# GSR.net
KiCad netlist of a schematic drawn in Altium Designer
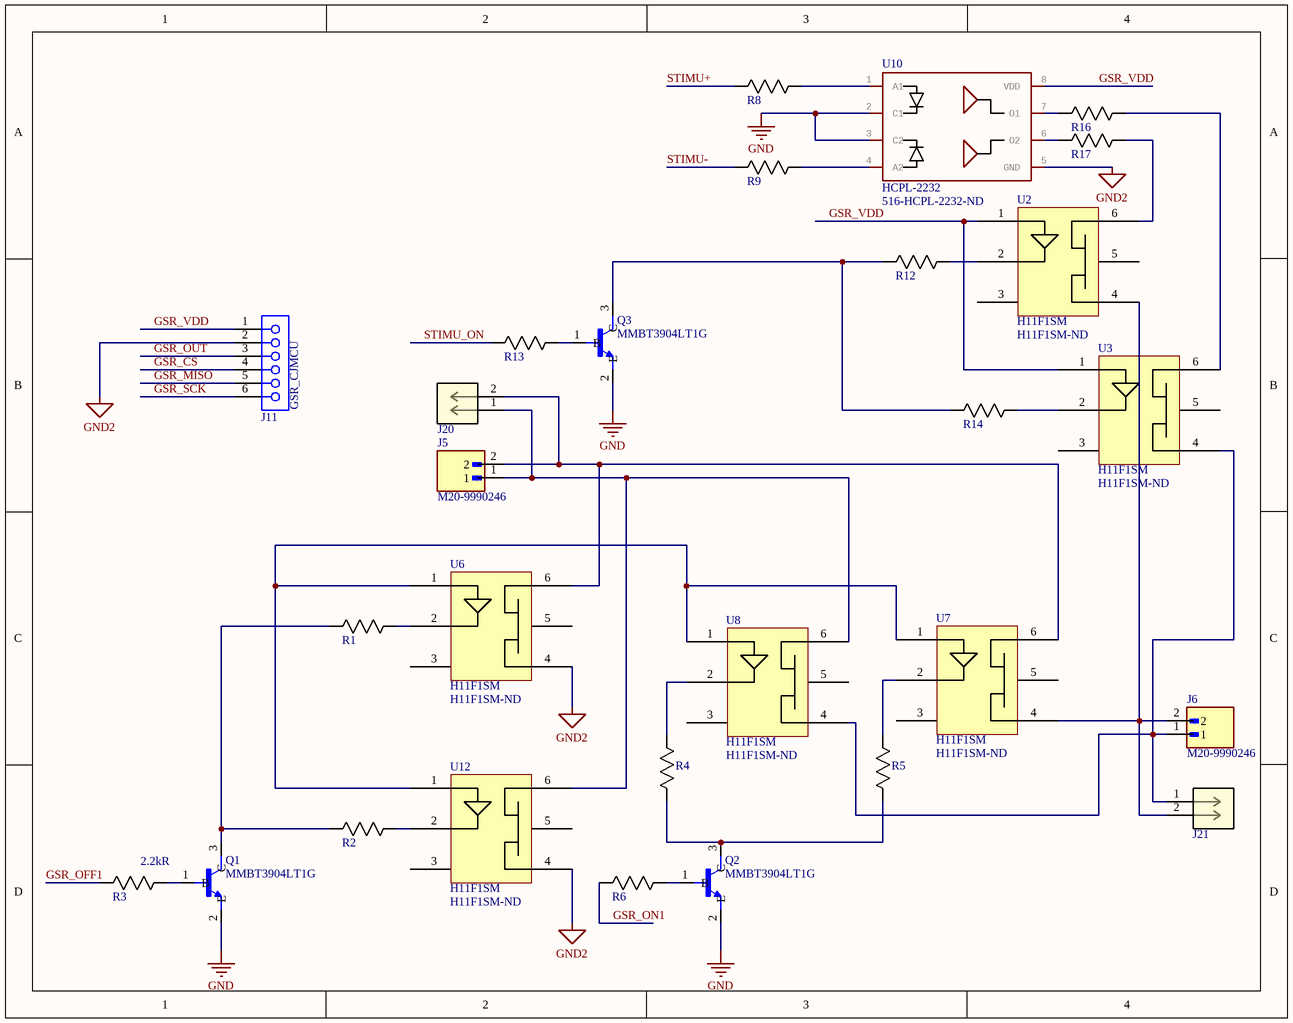
[diagram p0: GSR.SchDoc]

(export (version "E")
  (design (tool "Eeschema 10.0.6"))
  (components
    (comp (ref "J5")
      (value "M20-9990246")
      (footprint "HARWIN_M20-9990246")
      (description "2.54mm (0.1) Pitch SIL Vertical Throughboard Pin Header, 6.1mm mating pin height, tin, 2 contacts")
      (fields (field (name "MF") "Harwin"))
      (libsource (lib "koncept") (part "M20-9990246"))
    )
    (comp (ref "J6")
      (value "M20-9990246")
      (footprint "HARWIN_M20-9990246")
      (description "2.54mm (0.1) Pitch SIL Vertical Throughboard Pin Header, 6.1mm mating pin height, tin, 2 contacts")
      (fields (field (name "MF") "Harwin"))
      (libsource (lib "") (part "M20-9990246_1"))
    )
    (comp (ref "J11")
      (value "61300611821")
      (footprint "HEADER_SOCKET_6")
      (description "WR-PHD Socket Header, THT, Vertical, pitch 2.54mm, 1 Row, 6P")
      (fields (field (name "MANUFACTURER") "Wurth Elektronik"))
      (libsource (lib "Connectors") (part "HEADER_SOCKET_6"))
    )
    (comp (ref "J20")
      (value "B2P-VH")
      (footprint "CONN_B2P-VH_JST")
      (description "VH Non-RoHS Compliant 2003 Vertical Connector Header -25C~85C 10A 250V 0.303 7.70mm")
      (fields (field (name "MANUFACTURER") "JST"))
      (libsource (lib "") (part "B2P-VH_1"))
    )
    (comp (ref "J21")
      (value "B2P-VH")
      (footprint "CONN_B2P-VH_JST")
      (description "VH Non-RoHS Compliant 2003 Vertical Connector Header -25C~85C 10A 250V 0.303 7.70mm")
      (fields (field (name "MANUFACTURER") "JST"))
      (libsource (lib "Connectors") (part "B2P-VH"))
    )
    (comp (ref "Q1")
      (value "MMBT3904LT1G")
      (footprint "SOT95P240X111-3N")
      (fields (field (name "MF") "ON Semiconductor"))
      (libsource (lib "Passive") (part "MMBT3904LT1G"))
    )
    (comp (ref "Q2")
      (value "MMBT3904LT1G")
      (footprint "SOT95P240X111-3N")
      (fields (field (name "MF") "ON Semiconductor"))
      (libsource (lib "Passive") (part "MMBT3904LT1G"))
    )
    (comp (ref "Q3")
      (value "MMBT3904LT1G")
      (footprint "SOT95P240X111-3N")
      (fields (field (name "MF") "ON Semiconductor"))
      (libsource (lib "Passive") (part "MMBT3904LT1G"))
    )
    (comp (ref "R1")
      (value "RMCF1206FT220R")
      (footprint "STA_RMCF1206_STP-L")
      (description "No Description Available")
      (fields (field (name "COPYRIGHT") "Copyright (C) 2025 Ultra Librarian. All rights reserved."))
      (libsource (lib "Passive") (part "RMCF1206FT220R"))
    )
    (comp (ref "R2")
      (value "RMCF1206FT220R")
      (footprint "STA_RMCF1206_STP-L")
      (description "No Description Available")
      (fields (field (name "COPYRIGHT") "Copyright (C) 2025 Ultra Librarian. All rights reserved."))
      (libsource (lib "Passive") (part "RMCF1206FT220R"))
    )
    (comp (ref "R3")
      (value "CRGCQ1206F2K2")
      (footprint "STA_RMCF1206_STP-L")
      (description "SMD Chip Resistor, 2.2 kOhm, ± 1%, 250 mW, 1206 [3216 Metric], Thick Film, General Purpose")
      (fields (field (name "MANUFACTURER") "TE Connectivity") (field (name "RESISTANCE") "2.2kR"))
      (libsource (lib "Passive") (part "R1206F2K2"))
    )
    (comp (ref "R4")
      (value "RMCF1206FT220R")
      (footprint "STA_RMCF1206_STP-L")
      (description "No Description Available")
      (fields (field (name "COPYRIGHT") "Copyright (C) 2025 Ultra Librarian. All rights reserved."))
      (libsource (lib "Passive") (part "RMCF1206FT220R"))
    )
    (comp (ref "R5")
      (value "RMCF1206FT220R")
      (footprint "STA_RMCF1206_STP-L")
      (description "No Description Available")
      (fields (field (name "COPYRIGHT") "Copyright (C) 2025 Ultra Librarian. All rights reserved."))
      (libsource (lib "Passive") (part "RMCF1206FT220R"))
    )
    (comp (ref "R6")
      (value "CRGCQ1206F2K2")
      (footprint "STA_RMCF1206_STP-L")
      (description "SMD Chip Resistor, 2.2 kOhm, ± 1%, 250 mW, 1206 [3216 Metric], Thick Film, General Purpose")
      (fields (field (name "MANUFACTURER") "TE Connectivity"))
      (libsource (lib "Passive") (part "R1206F2K2"))
    )
    (comp (ref "R8")
      (value "RMCF1206FT220R")
      (footprint "STA_RMCF1206_STP-L")
      (description "No Description Available")
      (fields (field (name "COPYRIGHT") "Copyright (C) 2025 Ultra Librarian. All rights reserved."))
      (libsource (lib "Passive") (part "RMCF1206FT220R"))
    )
    (comp (ref "R9")
      (value "RMCF1206FT220R")
      (footprint "STA_RMCF1206_STP-L")
      (description "No Description Available")
      (fields (field (name "COPYRIGHT") "Copyright (C) 2025 Ultra Librarian. All rights reserved."))
      (libsource (lib "Passive") (part "RMCF1206FT220R"))
    )
    (comp (ref "R12")
      (value "RMCF1206FT220R")
      (footprint "STA_RMCF1206_STP-L")
      (description "No Description Available")
      (fields (field (name "COPYRIGHT") "Copyright (C) 2025 Ultra Librarian. All rights reserved."))
      (libsource (lib "Passive") (part "RMCF1206FT220R"))
    )
    (comp (ref "R13")
      (value "CRGCQ1206F2K2")
      (footprint "STA_RMCF1206_STP-L")
      (description "SMD Chip Resistor, 2.2 kOhm, ± 1%, 250 mW, 1206 [3216 Metric], Thick Film, General Purpose")
      (fields (field (name "MANUFACTURER") "TE Connectivity"))
      (libsource (lib "Passive") (part "R1206F2K2"))
    )
    (comp (ref "R14")
      (value "RMCF1206FT220R")
      (footprint "STA_RMCF1206_STP-L")
      (description "No Description Available")
      (fields (field (name "COPYRIGHT") "Copyright (C) 2025 Ultra Librarian. All rights reserved."))
      (libsource (lib "Passive") (part "RMCF1206FT220R"))
    )
    (comp (ref "R16")
      (value "CRGCQ1206F2K2")
      (footprint "STA_RMCF1206_STP-L")
      (description "SMD Chip Resistor, 2.2 kOhm, ± 1%, 250 mW, 1206 [3216 Metric], Thick Film, General Purpose")
      (fields (field (name "MANUFACTURER") "TE Connectivity"))
      (libsource (lib "Passive") (part "R1206F2K2"))
    )
    (comp (ref "R17")
      (value "CRGCQ1206F2K2")
      (footprint "STA_RMCF1206_STP-L")
      (description "SMD Chip Resistor, 2.2 kOhm, ± 1%, 250 mW, 1206 [3216 Metric], Thick Film, General Purpose")
      (fields (field (name "MANUFACTURER") "TE Connectivity"))
      (libsource (lib "Passive") (part "R1206F2K2"))
    )
    (comp (ref "U2")
      (value "H11F1SM")
      (footprint "OPTOCOUPLER_H11F3SR2M")
      (description "Optocoupler DC-IN 1-CH Transistor DC-OUT 6-Pin PDIP SMD White Bulk")
      (fields (field (name "MANUFACTURER") "onsemi") (field (name "SUPPLIER PART NUMBER 1") "H11F1SM-ND"))
      (libsource (lib "koncept") (part "H11F1SM"))
    )
    (comp (ref "U3")
      (value "H11F1SM")
      (footprint "OPTOCOUPLER_H11F3SR2M")
      (description "Optocoupler DC-IN 1-CH Transistor DC-OUT 6-Pin PDIP SMD White Bulk")
      (fields (field (name "MANUFACTURER") "onsemi") (field (name "SUPPLIER PART NUMBER 1") "H11F1SM-ND"))
      (libsource (lib "koncept") (part "H11F1SM"))
    )
    (comp (ref "U6")
      (value "H11F1SM")
      (footprint "OPTOCOUPLER_H11F3SR2M")
      (description "Optocoupler DC-IN 1-CH Transistor DC-OUT 6-Pin PDIP SMD White Bulk")
      (fields (field (name "MANUFACTURER") "onsemi") (field (name "SUPPLIER PART NUMBER 1") "H11F1SM-ND"))
      (libsource (lib "koncept") (part "H11F1SM"))
    )
    (comp (ref "U7")
      (value "H11F1SM")
      (footprint "OPTOCOUPLER_H11F3SR2M")
      (description "Optocoupler DC-IN 1-CH Transistor DC-OUT 6-Pin PDIP SMD White Bulk")
      (fields (field (name "MANUFACTURER") "onsemi") (field (name "SUPPLIER PART NUMBER 1") "H11F1SM-ND"))
      (libsource (lib "koncept") (part "H11F1SM"))
    )
    (comp (ref "U8")
      (value "H11F1SM")
      (footprint "OPTOCOUPLER_H11F3SR2M")
      (description "Optocoupler DC-IN 1-CH Transistor DC-OUT 6-Pin PDIP SMD White Bulk")
      (fields (field (name "MANUFACTURER") "onsemi") (field (name "SUPPLIER PART NUMBER 1") "H11F1SM-ND"))
      (libsource (lib "koncept") (part "H11F1SM"))
    )
    (comp (ref "U10")
      (value "HCPL-2232")
      (footprint "DIL08")
      (description "Optocoupler Logic Output Totem-Pole DC Input 2 Channel 8-Pin Plastic Dip Tube")
      (fields
        (field (name "MANUFACTURER") "Broadcom Avago")
        (field (name "SUPPLIER PART NUMBER 1") "516-HCPL-2232-ND")
      )
      (libsource (lib "koncept") (part "HCPL-2232"))
    )
    (comp (ref "U12")
      (value "H11F1SM")
      (footprint "OPTOCOUPLER_H11F3SR2M")
      (description "Optocoupler DC-IN 1-CH Transistor DC-OUT 6-Pin PDIP SMD White Bulk")
      (fields (field (name "MANUFACTURER") "onsemi") (field (name "SUPPLIER PART NUMBER 1") "H11F1SM-ND"))
      (libsource (lib "koncept") (part "H11F1SM"))
    )
  )
  (nets
    (net (code "1") (name "/GSR_CS") (class "Default")
      (node (ref "J11") (pin "4") (pinfunction "4_4") (pintype "passive"))
    )
    (net (code "2") (name "/GSR_MISO") (class "Default")
      (node (ref "J11") (pin "5") (pinfunction "5_5") (pintype "passive"))
    )
    (net (code "3") (name "/GSR_OFF1") (class "Default")
      (node (ref "R3") (pin "1") (pinfunction "1_1") (pintype "passive"))
    )
    (net (code "4") (name "/GSR_ON1") (class "Default")
      (node (ref "R6") (pin "1") (pinfunction "1_1") (pintype "passive"))
    )
    (net (code "5") (name "/GSR_OUT") (class "Default")
      (node (ref "J11") (pin "3") (pinfunction "3_3") (pintype "passive"))
    )
    (net (code "6") (name "/GSR_SCK") (class "Default")
      (node (ref "J11") (pin "6") (pinfunction "6_6") (pintype "passive"))
    )
    (net (code "7") (name "/GSR_VDD") (class "Default")
      (node (ref "J11") (pin "1") (pinfunction "1_1") (pintype "passive"))
      (node (ref "U10") (pin "8") (pinfunction "VDD_8") (pintype "power_in"))
      (node (ref "U2") (pin "1") (pinfunction "1_1") (pintype "passive"))
      (node (ref "U3") (pin "1") (pinfunction "1_1") (pintype "passive"))
    )
    (net (code "8") (name "/STIMU+") (class "Default")
      (node (ref "R8") (pin "1") (pinfunction "1_1") (pintype "passive"))
    )
    (net (code "9") (name "/STIMU-") (class "Default")
      (node (ref "R9") (pin "1") (pinfunction "1_1") (pintype "passive"))
    )
    (net (code "10") (name "/STIMU_ON") (class "Default")
      (node (ref "R13") (pin "1") (pinfunction "1_1") (pintype "passive"))
    )
    (net (code "11") (name "GND") (class "Default")
      (node (ref "Q1") (pin "2") (pinfunction "E_2") (pintype "passive"))
      (node (ref "Q2") (pin "2") (pinfunction "E_2") (pintype "passive"))
      (node (ref "Q3") (pin "2") (pinfunction "E_2") (pintype "passive"))
      (node (ref "U10") (pin "2") (pinfunction "C1_2") (pintype "power_in"))
      (node (ref "U10") (pin "3") (pinfunction "C2_3") (pintype "power_in"))
    )
    (net (code "12") (name "GND2") (class "Default")
      (node (ref "J11") (pin "2") (pinfunction "2_2") (pintype "passive"))
      (node (ref "U10") (pin "5") (pinfunction "GND_5") (pintype "power_in"))
      (node (ref "U12") (pin "4") (pinfunction "4_4") (pintype "passive"))
      (node (ref "U6") (pin "4") (pinfunction "4_4") (pintype "passive"))
    )
    (net (code "13") (name "Net-(J20-Pad1)") (class "Default")
      (node (ref "J20") (pin "1") (pinfunction "1_1") (pintype "passive"))
      (node (ref "J5") (pin "1") (pinfunction "1_1") (pintype "passive"))
      (node (ref "U12") (pin "6") (pinfunction "6_6") (pintype "passive"))
      (node (ref "U8") (pin "6") (pinfunction "6_6") (pintype "passive"))
    )
    (net (code "14") (name "Net-(J20-Pad2)") (class "Default")
      (node (ref "J20") (pin "2") (pinfunction "2_2") (pintype "passive"))
      (node (ref "J5") (pin "2") (pinfunction "2_2") (pintype "passive"))
      (node (ref "U6") (pin "6") (pinfunction "6_6") (pintype "passive"))
      (node (ref "U7") (pin "6") (pinfunction "6_6") (pintype "passive"))
    )
    (net (code "15") (name "Net-(J21-Pad1)") (class "Default")
      (node (ref "J21") (pin "1") (pinfunction "1_1") (pintype "passive"))
      (node (ref "J6") (pin "1") (pinfunction "1_1") (pintype "passive"))
      (node (ref "U3") (pin "4") (pinfunction "4_4") (pintype "passive"))
      (node (ref "U8") (pin "4") (pinfunction "4_4") (pintype "passive"))
    )
    (net (code "16") (name "Net-(J21-Pad2)") (class "Default")
      (node (ref "J21") (pin "2") (pinfunction "2_2") (pintype "passive"))
      (node (ref "J6") (pin "2") (pinfunction "2_2") (pintype "passive"))
      (node (ref "U2") (pin "4") (pinfunction "4_4") (pintype "passive"))
      (node (ref "U7") (pin "4") (pinfunction "4_4") (pintype "passive"))
    )
    (net (code "17") (name "Net-(Q1-B)") (class "Default")
      (node (ref "Q1") (pin "1") (pinfunction "B_1") (pintype "passive"))
      (node (ref "R3") (pin "2") (pinfunction "2_2") (pintype "passive"))
    )
    (net (code "18") (name "Net-(Q1-C)") (class "Default")
      (node (ref "Q1") (pin "3") (pinfunction "C_3") (pintype "passive"))
      (node (ref "R1") (pin "1") (pinfunction "1_1") (pintype "passive"))
      (node (ref "R2") (pin "1") (pinfunction "1_1") (pintype "passive"))
    )
    (net (code "19") (name "Net-(Q2-B)") (class "Default")
      (node (ref "Q2") (pin "1") (pinfunction "B_1") (pintype "passive"))
      (node (ref "R6") (pin "2") (pinfunction "2_2") (pintype "passive"))
    )
    (net (code "20") (name "Net-(Q2-C)") (class "Default")
      (node (ref "Q2") (pin "3") (pinfunction "C_3") (pintype "passive"))
      (node (ref "R4") (pin "1") (pinfunction "1_1") (pintype "passive"))
      (node (ref "R5") (pin "1") (pinfunction "1_1") (pintype "passive"))
    )
    (net (code "21") (name "Net-(Q3-B)") (class "Default")
      (node (ref "Q3") (pin "1") (pinfunction "B_1") (pintype "passive"))
      (node (ref "R13") (pin "2") (pinfunction "2_2") (pintype "passive"))
    )
    (net (code "22") (name "Net-(Q3-C)") (class "Default")
      (node (ref "Q3") (pin "3") (pinfunction "C_3") (pintype "passive"))
      (node (ref "R12") (pin "2") (pinfunction "2_2") (pintype "passive"))
      (node (ref "R14") (pin "2") (pinfunction "2_2") (pintype "passive"))
    )
    (net (code "23") (name "Net-(R1-Pad2)") (class "Default")
      (node (ref "R1") (pin "2") (pinfunction "2_2") (pintype "passive"))
      (node (ref "U6") (pin "2") (pinfunction "2_2") (pintype "passive"))
    )
    (net (code "24") (name "Net-(R2-Pad2)") (class "Default")
      (node (ref "R2") (pin "2") (pinfunction "2_2") (pintype "passive"))
      (node (ref "U12") (pin "2") (pinfunction "2_2") (pintype "passive"))
    )
    (net (code "25") (name "Net-(R4-Pad2)") (class "Default")
      (node (ref "R4") (pin "2") (pinfunction "2_2") (pintype "passive"))
      (node (ref "U8") (pin "2") (pinfunction "2_2") (pintype "passive"))
    )
    (net (code "26") (name "Net-(R5-Pad2)") (class "Default")
      (node (ref "R5") (pin "2") (pinfunction "2_2") (pintype "passive"))
      (node (ref "U7") (pin "2") (pinfunction "2_2") (pintype "passive"))
    )
    (net (code "27") (name "Net-(R12-Pad1)") (class "Default")
      (node (ref "R12") (pin "1") (pinfunction "1_1") (pintype "passive"))
      (node (ref "U2") (pin "2") (pinfunction "2_2") (pintype "passive"))
    )
    (net (code "28") (name "Net-(R14-Pad1)") (class "Default")
      (node (ref "R14") (pin "1") (pinfunction "1_1") (pintype "passive"))
      (node (ref "U3") (pin "2") (pinfunction "2_2") (pintype "passive"))
    )
    (net (code "29") (name "Net-(R16-Pad2)") (class "Default")
      (node (ref "R16") (pin "2") (pinfunction "2_2") (pintype "passive"))
      (node (ref "U3") (pin "6") (pinfunction "6_6") (pintype "passive"))
    )
    (net (code "30") (name "Net-(R17-Pad2)") (class "Default")
      (node (ref "R17") (pin "2") (pinfunction "2_2") (pintype "passive"))
      (node (ref "U2") (pin "6") (pinfunction "6_6") (pintype "passive"))
    )
    (net (code "31") (name "Net-(U10-A1)") (class "Default")
      (node (ref "R8") (pin "2") (pinfunction "2_2") (pintype "passive"))
      (node (ref "U10") (pin "1") (pinfunction "A1_1") (pintype "power_in"))
    )
    (net (code "32") (name "Net-(U10-A2)") (class "Default")
      (node (ref "R9") (pin "2") (pinfunction "2_2") (pintype "passive"))
      (node (ref "U10") (pin "4") (pinfunction "A2_4") (pintype "power_in"))
    )
    (net (code "33") (name "Net-(U10-O1)") (class "Default")
      (node (ref "R16") (pin "1") (pinfunction "1_1") (pintype "passive"))
      (node (ref "U10") (pin "7") (pinfunction "O1_7") (pintype "power_in"))
    )
    (net (code "34") (name "Net-(U10-O2)") (class "Default")
      (node (ref "R17") (pin "1") (pinfunction "1_1") (pintype "passive"))
      (node (ref "U10") (pin "6") (pinfunction "O2_6") (pintype "power_in"))
    )
    (net (code "35") (name "Net-(U12-Pad1)") (class "Default")
      (node (ref "U12") (pin "1") (pinfunction "1_1") (pintype "passive"))
      (node (ref "U6") (pin "1") (pinfunction "1_1") (pintype "passive"))
      (node (ref "U7") (pin "1") (pinfunction "1_1") (pintype "passive"))
      (node (ref "U8") (pin "1") (pinfunction "1_1") (pintype "passive"))
    )
    (net (code "36") (name "unconnected-(U2-Pad3)") (class "Default")
      (node (ref "U2") (pin "3") (pinfunction "3_3") (pintype "passive"))
    )
    (net (code "37") (name "unconnected-(U2-Pad5)") (class "Default")
      (node (ref "U2") (pin "5") (pinfunction "5_5") (pintype "passive"))
    )
    (net (code "38") (name "unconnected-(U3-Pad3)") (class "Default")
      (node (ref "U3") (pin "3") (pinfunction "3_3") (pintype "passive"))
    )
    (net (code "39") (name "unconnected-(U3-Pad5)") (class "Default")
      (node (ref "U3") (pin "5") (pinfunction "5_5") (pintype "passive"))
    )
    (net (code "40") (name "unconnected-(U6-Pad3)") (class "Default")
      (node (ref "U6") (pin "3") (pinfunction "3_3") (pintype "passive"))
    )
    (net (code "41") (name "unconnected-(U6-Pad5)") (class "Default")
      (node (ref "U6") (pin "5") (pinfunction "5_5") (pintype "passive"))
    )
    (net (code "42") (name "unconnected-(U7-Pad3)") (class "Default")
      (node (ref "U7") (pin "3") (pinfunction "3_3") (pintype "passive"))
    )
    (net (code "43") (name "unconnected-(U7-Pad5)") (class "Default")
      (node (ref "U7") (pin "5") (pinfunction "5_5") (pintype "passive"))
    )
    (net (code "44") (name "unconnected-(U8-Pad3)") (class "Default")
      (node (ref "U8") (pin "3") (pinfunction "3_3") (pintype "passive"))
    )
    (net (code "45") (name "unconnected-(U8-Pad5)") (class "Default")
      (node (ref "U8") (pin "5") (pinfunction "5_5") (pintype "passive"))
    )
    (net (code "46") (name "unconnected-(U12-Pad3)") (class "Default")
      (node (ref "U12") (pin "3") (pinfunction "3_3") (pintype "passive"))
    )
    (net (code "47") (name "unconnected-(U12-Pad5)") (class "Default")
      (node (ref "U12") (pin "5") (pinfunction "5_5") (pintype "passive"))
    )
  )
)
